# Sheet_2.net
KiCad netlist of a schematic drawn in Altium Designer
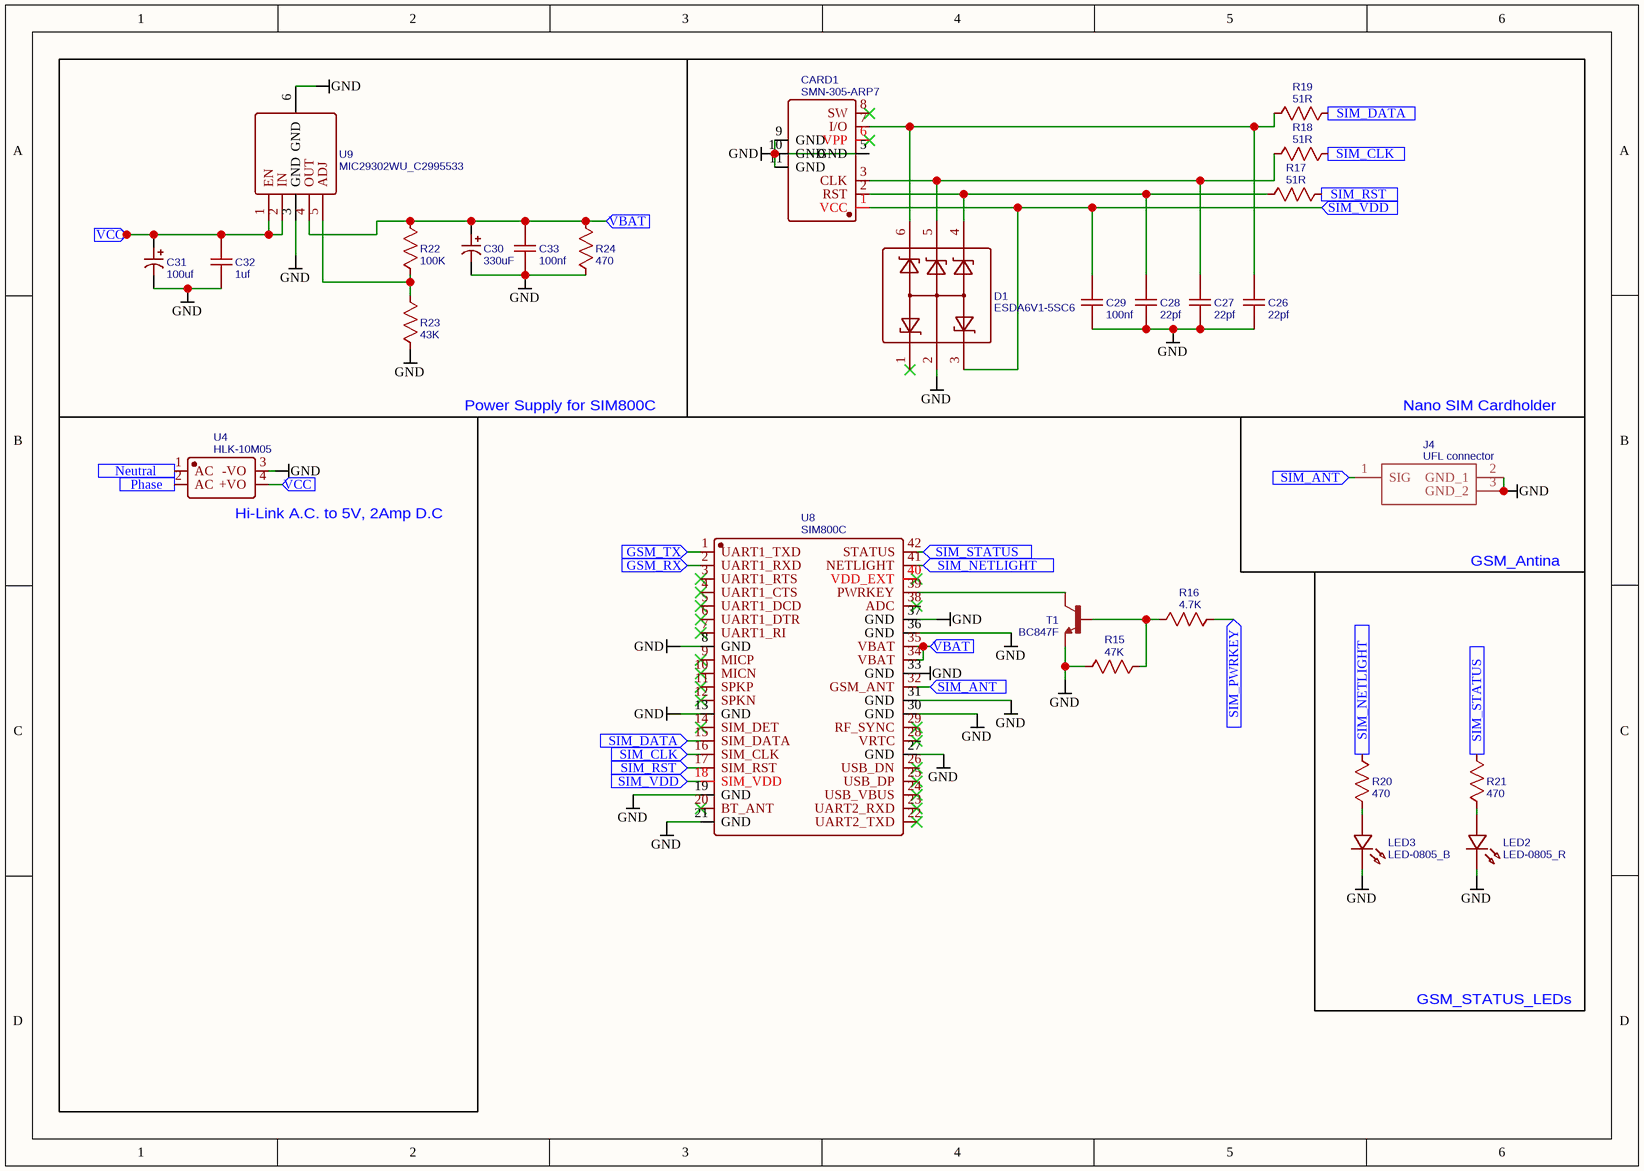
[diagram p0: Sheet_2.schdoc]

(export (version "E")
  (design (tool "Eeschema 10.0.6"))
  (components
    (comp (ref "C26")
      (value "22pf")
      (fields (field (name "CONTRIBUTOR") "LCEDA_Lib"))
      (libsource (lib "altium-import") (part "root_1_22pf_"))
    )
    (comp (ref "C27")
      (value "22pf")
      (fields (field (name "CONTRIBUTOR") "LCEDA_Lib"))
      (libsource (lib "altium-import") (part "root_1_22pf_"))
    )
    (comp (ref "C28")
      (value "22pf")
      (fields (field (name "CONTRIBUTOR") "LCEDA_Lib"))
      (libsource (lib "altium-import") (part "root_1_22pf_"))
    )
    (comp (ref "C29")
      (value "100nf")
      (fields (field (name "CONTRIBUTOR") "LCEDA_Lib"))
      (libsource (lib "altium-import") (part "root_1_100nf_"))
    )
    (comp (ref "C30")
      (value "330uF")
      (fields
        (field (name "MANUFACTURER") "KNSCHA(科尼盛)")
        (field (name "MANUFACTURER PART") "LZ330UF35V90RV0141")
        (field (name "CONTRIBUTOR") "lcsc")
      )
      (libsource (lib "altium-import") (part "root_3_330uF_"))
    )
    (comp (ref "C31")
      (value "100uf")
      (fields
        (field (name "MANUFACTURER") "KNSCHA(科尼盛)")
        (field (name "MANUFACTURER PART") "LZ330UF35V90RV0141")
        (field (name "CONTRIBUTOR") "lcsc")
      )
      (libsource (lib "altium-import") (part "root_3_100uf_"))
    )
    (comp (ref "C32")
      (value "1uf")
      (fields (field (name "CONTRIBUTOR") "LCEDA_Lib"))
      (libsource (lib "altium-import") (part "root_1_1uf_"))
    )
    (comp (ref "C33")
      (value "100nf")
      (fields (field (name "CONTRIBUTOR") "LCEDA_Lib"))
      (libsource (lib "altium-import") (part "root_1_100nf_"))
    )
    (comp (ref "CARD1")
      (value "SMN-305-ARP7")
      (fields (field (name "MANUFACTURER") "XUNPU(讯普)") (field (name "CONTRIBUTOR") "LCSC"))
      (libsource (lib "altium-import") (part "root_2_SMN-305-ARP7_"))
    )
    (comp (ref "D1")
      (value "ESDA6V1-5SC6")
      (fields (field (name "MANUFACTURER") "ST(意法半导体)"))
      (libsource (lib "altium-import") (part "root_1_ESDA6V1-5SC6_"))
    )
    (comp (ref "J4")
      (value "UFL connector")
      (fields (field (name "CONTRIBUTOR") "BzuV"))
      (libsource (lib "altium-import") (part "root_0_UFL connector_"))
    )
    (comp (ref "LED2")
      (value "LED-0805_R")
      (fields
        (field (name "MANUFACTURER") "EVERLIGHT(台湾亿光)")
        (field (name "MANUFACTURER PART") "17-21SURC/S530-A3/TR8")
        (field (name "CONTRIBUTOR") "LCEDA_Lib")
      )
      (libsource (lib "altium-import") (part "root_3_LED-0805_R_"))
    )
    (comp (ref "LED3")
      (value "LED-0805_B")
      (fields
        (field (name "MANUFACTURER") "方舟 ARKLED")
        (field (name "MANUFACTURER PART") "D-B080508B1-KS2")
        (field (name "CONTRIBUTOR") "LCEDA_Lib")
      )
      (libsource (lib "altium-import") (part "root_3_LED-0805_B_"))
    )
    (comp (ref "R15")
      (value "47K")
      (fields (field (name "CONTRIBUTOR") "LCEDA_Lib"))
      (libsource (lib "altium-import") (part "root_0_47K_"))
    )
    (comp (ref "R16")
      (value "4.7K")
      (fields (field (name "CONTRIBUTOR") "LCEDA_Lib"))
      (libsource (lib "altium-import") (part "root_0_4.7K_"))
    )
    (comp (ref "R17")
      (value "51R")
      (fields (field (name "CONTRIBUTOR") "LCEDA_Lib"))
      (libsource (lib "altium-import") (part "root_0_51R_"))
    )
    (comp (ref "R18")
      (value "51R")
      (fields (field (name "CONTRIBUTOR") "LCEDA_Lib"))
      (libsource (lib "altium-import") (part "root_0_51R_"))
    )
    (comp (ref "R19")
      (value "51R")
      (fields (field (name "CONTRIBUTOR") "LCEDA_Lib"))
      (libsource (lib "altium-import") (part "root_0_51R_"))
    )
    (comp (ref "R20")
      (value "470")
      (fields (field (name "CONTRIBUTOR") "LCEDA_Lib"))
      (libsource (lib "altium-import") (part "root_3_470_"))
    )
    (comp (ref "R21")
      (value "470")
      (fields (field (name "CONTRIBUTOR") "LCEDA_Lib"))
      (libsource (lib "altium-import") (part "root_3_470_"))
    )
    (comp (ref "R22")
      (value "100K")
      (fields (field (name "CONTRIBUTOR") "LCEDA_Lib"))
      (libsource (lib "altium-import") (part "root_1_100K_"))
    )
    (comp (ref "R23")
      (value "43K")
      (fields (field (name "CONTRIBUTOR") "LCEDA_Lib"))
      (libsource (lib "altium-import") (part "root_1_43K_"))
    )
    (comp (ref "R24")
      (value "470")
      (fields (field (name "CONTRIBUTOR") "LCEDA_Lib"))
      (libsource (lib "altium-import") (part "root_3_470_"))
    )
    (comp (ref "T1") (value "BC847F") (libsource (lib "altium-import") (part "root_0_BC847F_")))
    (comp (ref "U4")
      (value "HLK-10M05")
      (fields (field (name "MANUFACTURER") "HI-LINK(海凌科)") (field (name "CONTRIBUTOR") "LCSC"))
      (libsource (lib "altium-import") (part "root_0_HLK-10M05_"))
    )
    (comp (ref "U8")
      (value "SIM800C")
      (fields (field (name "CONTRIBUTOR") "LCSC"))
      (libsource (lib "altium-import") (part "root_0_SIM800C_"))
    )
    (comp (ref "U9")
      (value "MIC29302WU_C2995533")
      (fields
        (field (name "MANUFACTURER") "UMW(广东友台半导体)")
        (field (name "MANUFACTURER PART") "MIC29302WU")
        (field (name "CONTRIBUTOR") "lcsc")
      )
      (libsource (lib "altium-import") (part "root_1_MIC29302WU_C2995533_"))
    )
  )
  (nets
    (net (code "1") (name "/GSM_RX") (class "Default")
      (node (ref "U8") (pin "2") (pinfunction "UART1_RXD_2") (pintype "passive"))
    )
    (net (code "2") (name "/GSM_TX") (class "Default")
      (node (ref "U8") (pin "1") (pinfunction "UART1_TXD_1") (pintype "passive"))
    )
    (net (code "3") (name "/Neutral") (class "Default")
      (node (ref "U4") (pin "1") (pinfunction "AC_1") (pintype "passive"))
    )
    (net (code "4") (name "/Phase") (class "Default")
      (node (ref "U4") (pin "2") (pinfunction "AC_2") (pintype "passive"))
    )
    (net (code "5") (name "/SIM_ANT") (class "Default")
      (node (ref "J4") (pin "1") (pinfunction "SIG_1") (pintype "passive"))
      (node (ref "U8") (pin "32") (pinfunction "GSM_ANT_32") (pintype "passive"))
    )
    (net (code "6") (name "/SIM_CLK") (class "Default")
      (node (ref "R18") (pin "2") (pinfunction "2_2") (pintype "passive"))
      (node (ref "U8") (pin "16") (pinfunction "SIM_CLK_16") (pintype "passive"))
    )
    (net (code "7") (name "/SIM_DATA") (class "Default")
      (node (ref "R19") (pin "2") (pinfunction "2_2") (pintype "passive"))
      (node (ref "U8") (pin "15") (pinfunction "SIM_DATA_15") (pintype "passive"))
    )
    (net (code "8") (name "/SIM_NETLIGHT") (class "Default")
      (node (ref "R20") (pin "1") (pinfunction "1_1") (pintype "passive"))
      (node (ref "U8") (pin "41") (pinfunction "NETLIGHT_41") (pintype "passive"))
    )
    (net (code "9") (name "/SIM_PWRKEY") (class "Default")
      (node (ref "R16") (pin "2") (pinfunction "2_2") (pintype "passive"))
    )
    (net (code "10") (name "/SIM_RST") (class "Default")
      (node (ref "R17") (pin "2") (pinfunction "2_2") (pintype "passive"))
      (node (ref "U8") (pin "17") (pinfunction "SIM_RST_17") (pintype "passive"))
    )
    (net (code "11") (name "/SIM_STATUS") (class "Default")
      (node (ref "R21") (pin "1") (pinfunction "1_1") (pintype "passive"))
      (node (ref "U8") (pin "42") (pinfunction "STATUS_42") (pintype "passive"))
    )
    (net (code "12") (name "/SIM_VDD") (class "Default")
      (node (ref "C29") (pin "2") (pinfunction "2_2") (pintype "passive"))
      (node (ref "CARD1") (pin "1") (pinfunction "VCC_1") (pintype "passive"))
      (node (ref "D1") (pin "3") (pinfunction "IO2_3") (pintype "passive"))
      (node (ref "U8") (pin "18") (pinfunction "SIM_VDD_18") (pintype "passive"))
    )
    (net (code "13") (name "/VBAT") (class "Default")
      (node (ref "C30") (pin "1") (pinfunction "1_1") (pintype "passive"))
      (node (ref "C33") (pin "2") (pinfunction "2_2") (pintype "passive"))
      (node (ref "R22") (pin "2") (pinfunction "2_2") (pintype "passive"))
      (node (ref "R24") (pin "1") (pinfunction "1_1") (pintype "passive"))
      (node (ref "U8") (pin "34") (pinfunction "VBAT_34") (pintype "passive"))
      (node (ref "U8") (pin "35") (pinfunction "VBAT_35") (pintype "passive"))
      (node (ref "U9") (pin "4") (pinfunction "OUT_4") (pintype "passive"))
    )
    (net (code "14") (name "/VCC") (class "Default")
      (node (ref "C31") (pin "1") (pinfunction "1_1") (pintype "passive"))
      (node (ref "C32") (pin "2") (pinfunction "2_2") (pintype "passive"))
      (node (ref "U4") (pin "4") (pinfunction "+VO_4") (pintype "passive"))
      (node (ref "U9") (pin "1") (pinfunction "EN_1") (pintype "passive"))
      (node (ref "U9") (pin "2") (pinfunction "IN_2") (pintype "passive"))
    )
    (net (code "15") (name "GND") (class "Default")
      (node (ref "C26") (pin "1") (pinfunction "1_1") (pintype "passive"))
      (node (ref "C27") (pin "1") (pinfunction "1_1") (pintype "passive"))
      (node (ref "C28") (pin "1") (pinfunction "1_1") (pintype "passive"))
      (node (ref "C29") (pin "1") (pinfunction "1_1") (pintype "passive"))
      (node (ref "C30") (pin "2") (pinfunction "2_2") (pintype "passive"))
      (node (ref "C31") (pin "2") (pinfunction "2_2") (pintype "passive"))
      (node (ref "C32") (pin "1") (pinfunction "1_1") (pintype "passive"))
      (node (ref "C33") (pin "1") (pinfunction "1_1") (pintype "passive"))
      (node (ref "CARD1") (pin "10") (pinfunction "GND_10") (pintype "passive"))
      (node (ref "CARD1") (pin "11") (pinfunction "GND_11") (pintype "passive"))
      (node (ref "CARD1") (pin "5") (pinfunction "GND_5") (pintype "passive"))
      (node (ref "CARD1") (pin "9") (pinfunction "GND_9") (pintype "passive"))
      (node (ref "D1") (pin "2") (pinfunction "GND_2") (pintype "passive"))
      (node (ref "J4") (pin "2") (pinfunction "GND_1_2") (pintype "passive"))
      (node (ref "J4") (pin "3") (pinfunction "GND_2_3") (pintype "passive"))
      (node (ref "LED2") (pin "2") (pinfunction "2_2") (pintype "passive"))
      (node (ref "LED3") (pin "2") (pinfunction "2_2") (pintype "passive"))
      (node (ref "R15") (pin "1") (pinfunction "1_1") (pintype "passive"))
      (node (ref "R23") (pin "1") (pinfunction "1_1") (pintype "passive"))
      (node (ref "R24") (pin "2") (pinfunction "2_2") (pintype "passive"))
      (node (ref "T1") (pin "2") (pinfunction "E_2") (pintype "passive"))
      (node (ref "U4") (pin "3") (pinfunction "-VO_3") (pintype "passive"))
      (node (ref "U8") (pin "13") (pinfunction "GND_13") (pintype "passive"))
      (node (ref "U8") (pin "19") (pinfunction "GND_19") (pintype "passive"))
      (node (ref "U8") (pin "21") (pinfunction "GND_21") (pintype "passive"))
      (node (ref "U8") (pin "27") (pinfunction "GND_27") (pintype "passive"))
      (node (ref "U8") (pin "30") (pinfunction "GND_30") (pintype "passive"))
      (node (ref "U8") (pin "31") (pinfunction "GND_31") (pintype "passive"))
      (node (ref "U8") (pin "33") (pinfunction "GND_33") (pintype "passive"))
      (node (ref "U8") (pin "36") (pinfunction "GND_36") (pintype "passive"))
      (node (ref "U8") (pin "37") (pinfunction "GND_37") (pintype "passive"))
      (node (ref "U8") (pin "8") (pinfunction "GND_8") (pintype "passive"))
      (node (ref "U9") (pin "3") (pinfunction "GND_3") (pintype "passive"))
      (node (ref "U9") (pin "6") (pinfunction "GND_6") (pintype "passive"))
    )
    (net (code "16") (name "Net-(CARD1-CLK)") (class "Default")
      (node (ref "C27") (pin "2") (pinfunction "2_2") (pintype "passive"))
      (node (ref "CARD1") (pin "3") (pinfunction "CLK_3") (pintype "passive"))
      (node (ref "D1") (pin "5") (pinfunction "IO4_5") (pintype "passive"))
      (node (ref "R18") (pin "1") (pinfunction "1_1") (pintype "passive"))
    )
    (net (code "17") (name "Net-(CARD1-I{slash}O)") (class "Default")
      (node (ref "C26") (pin "2") (pinfunction "2_2") (pintype "passive"))
      (node (ref "CARD1") (pin "7") (pinfunction "I/O_7") (pintype "passive"))
      (node (ref "D1") (pin "6") (pinfunction "IO5_6") (pintype "passive"))
      (node (ref "R19") (pin "1") (pinfunction "1_1") (pintype "passive"))
    )
    (net (code "18") (name "Net-(CARD1-RST)") (class "Default")
      (node (ref "C28") (pin "2") (pinfunction "2_2") (pintype "passive"))
      (node (ref "CARD1") (pin "2") (pinfunction "RST_2") (pintype "passive"))
      (node (ref "D1") (pin "4") (pinfunction "IO3_4") (pintype "passive"))
      (node (ref "R17") (pin "1") (pinfunction "1_1") (pintype "passive"))
    )
    (net (code "19") (name "Net-(LED2-Pad1)") (class "Default")
      (node (ref "LED2") (pin "1") (pinfunction "1_1") (pintype "passive"))
      (node (ref "R21") (pin "2") (pinfunction "2_2") (pintype "passive"))
    )
    (net (code "20") (name "Net-(LED3-Pad1)") (class "Default")
      (node (ref "LED3") (pin "1") (pinfunction "1_1") (pintype "passive"))
      (node (ref "R20") (pin "2") (pinfunction "2_2") (pintype "passive"))
    )
    (net (code "21") (name "Net-(T1-B)") (class "Default")
      (node (ref "R15") (pin "2") (pinfunction "2_2") (pintype "passive"))
      (node (ref "R16") (pin "1") (pinfunction "1_1") (pintype "passive"))
      (node (ref "T1") (pin "1") (pinfunction "B_1") (pintype "passive"))
    )
    (net (code "22") (name "Net-(T1-C)") (class "Default")
      (node (ref "T1") (pin "3") (pinfunction "C_3") (pintype "passive"))
      (node (ref "U8") (pin "39") (pinfunction "PWRKEY_39") (pintype "passive"))
    )
    (net (code "23") (name "Net-(U9-ADJ)") (class "Default")
      (node (ref "R22") (pin "1") (pinfunction "1_1") (pintype "passive"))
      (node (ref "R23") (pin "2") (pinfunction "2_2") (pintype "passive"))
      (node (ref "U9") (pin "5") (pinfunction "ADJ_5") (pintype "passive"))
    )
    (net (code "24") (name "unconnected-(CARD1-SW-Pad8)") (class "Default")
      (node (ref "CARD1") (pin "8") (pinfunction "SW_8") (pintype "passive+no_connect"))
    )
    (net (code "25") (name "unconnected-(CARD1-VPP-Pad6)") (class "Default")
      (node (ref "CARD1") (pin "6") (pinfunction "VPP_6") (pintype "passive+no_connect"))
    )
    (net (code "26") (name "unconnected-(D1-IO1-Pad1)") (class "Default")
      (node (ref "D1") (pin "1") (pinfunction "IO1_1") (pintype "passive+no_connect"))
    )
    (net (code "27") (name "unconnected-(U8-ADC-Pad38)") (class "Default")
      (node (ref "U8") (pin "38") (pinfunction "ADC_38") (pintype "passive+no_connect"))
    )
    (net (code "28") (name "unconnected-(U8-BT_ANT-Pad20)") (class "Default")
      (node (ref "U8") (pin "20") (pinfunction "BT_ANT_20") (pintype "passive+no_connect"))
    )
    (net (code "29") (name "unconnected-(U8-MICN-Pad10)") (class "Default")
      (node (ref "U8") (pin "10") (pinfunction "MICN_10") (pintype "passive+no_connect"))
    )
    (net (code "30") (name "unconnected-(U8-MICP-Pad9)") (class "Default")
      (node (ref "U8") (pin "9") (pinfunction "MICP_9") (pintype "passive+no_connect"))
    )
    (net (code "31") (name "unconnected-(U8-RF_SYNC-Pad29)") (class "Default")
      (node (ref "U8") (pin "29") (pinfunction "RF_SYNC_29") (pintype "passive+no_connect"))
    )
    (net (code "32") (name "unconnected-(U8-SIM_DET-Pad14)") (class "Default")
      (node (ref "U8") (pin "14") (pinfunction "SIM_DET_14") (pintype "passive+no_connect"))
    )
    (net (code "33") (name "unconnected-(U8-SPKN-Pad12)") (class "Default")
      (node (ref "U8") (pin "12") (pinfunction "SPKN_12") (pintype "passive+no_connect"))
    )
    (net (code "34") (name "unconnected-(U8-SPKP-Pad11)") (class "Default")
      (node (ref "U8") (pin "11") (pinfunction "SPKP_11") (pintype "passive+no_connect"))
    )
    (net (code "35") (name "unconnected-(U8-UART1_CTS-Pad4)") (class "Default")
      (node (ref "U8") (pin "4") (pinfunction "UART1_CTS_4") (pintype "passive+no_connect"))
    )
    (net (code "36") (name "unconnected-(U8-UART1_DCD-Pad5)") (class "Default")
      (node (ref "U8") (pin "5") (pinfunction "UART1_DCD_5") (pintype "passive+no_connect"))
    )
    (net (code "37") (name "unconnected-(U8-UART1_DTR-Pad6)") (class "Default")
      (node (ref "U8") (pin "6") (pinfunction "UART1_DTR_6") (pintype "passive+no_connect"))
    )
    (net (code "38") (name "unconnected-(U8-UART1_RI-Pad7)") (class "Default")
      (node (ref "U8") (pin "7") (pinfunction "UART1_RI_7") (pintype "passive+no_connect"))
    )
    (net (code "39") (name "unconnected-(U8-UART1_RTS-Pad3)") (class "Default")
      (node (ref "U8") (pin "3") (pinfunction "UART1_RTS_3") (pintype "passive+no_connect"))
    )
    (net (code "40") (name "unconnected-(U8-UART2_RXD-Pad23)") (class "Default")
      (node (ref "U8") (pin "23") (pinfunction "UART2_RXD_23") (pintype "passive+no_connect"))
    )
    (net (code "41") (name "unconnected-(U8-UART2_TXD-Pad22)") (class "Default")
      (node (ref "U8") (pin "22") (pinfunction "UART2_TXD_22") (pintype "passive+no_connect"))
    )
    (net (code "42") (name "unconnected-(U8-USB_DN-Pad26)") (class "Default")
      (node (ref "U8") (pin "26") (pinfunction "USB_DN_26") (pintype "passive+no_connect"))
    )
    (net (code "43") (name "unconnected-(U8-USB_DP-Pad25)") (class "Default")
      (node (ref "U8") (pin "25") (pinfunction "USB_DP_25") (pintype "passive+no_connect"))
    )
    (net (code "44") (name "unconnected-(U8-USB_VBUS-Pad24)") (class "Default")
      (node (ref "U8") (pin "24") (pinfunction "USB_VBUS_24") (pintype "passive+no_connect"))
    )
    (net (code "45") (name "unconnected-(U8-VDD_EXT-Pad40)") (class "Default")
      (node (ref "U8") (pin "40") (pinfunction "VDD_EXT_40") (pintype "passive+no_connect"))
    )
    (net (code "46") (name "unconnected-(U8-VRTC-Pad28)") (class "Default")
      (node (ref "U8") (pin "28") (pinfunction "VRTC_28") (pintype "passive+no_connect"))
    )
  )
)
